# Vsense_Thermistor.net
KiCad netlist of a schematic drawn in Altium Designer
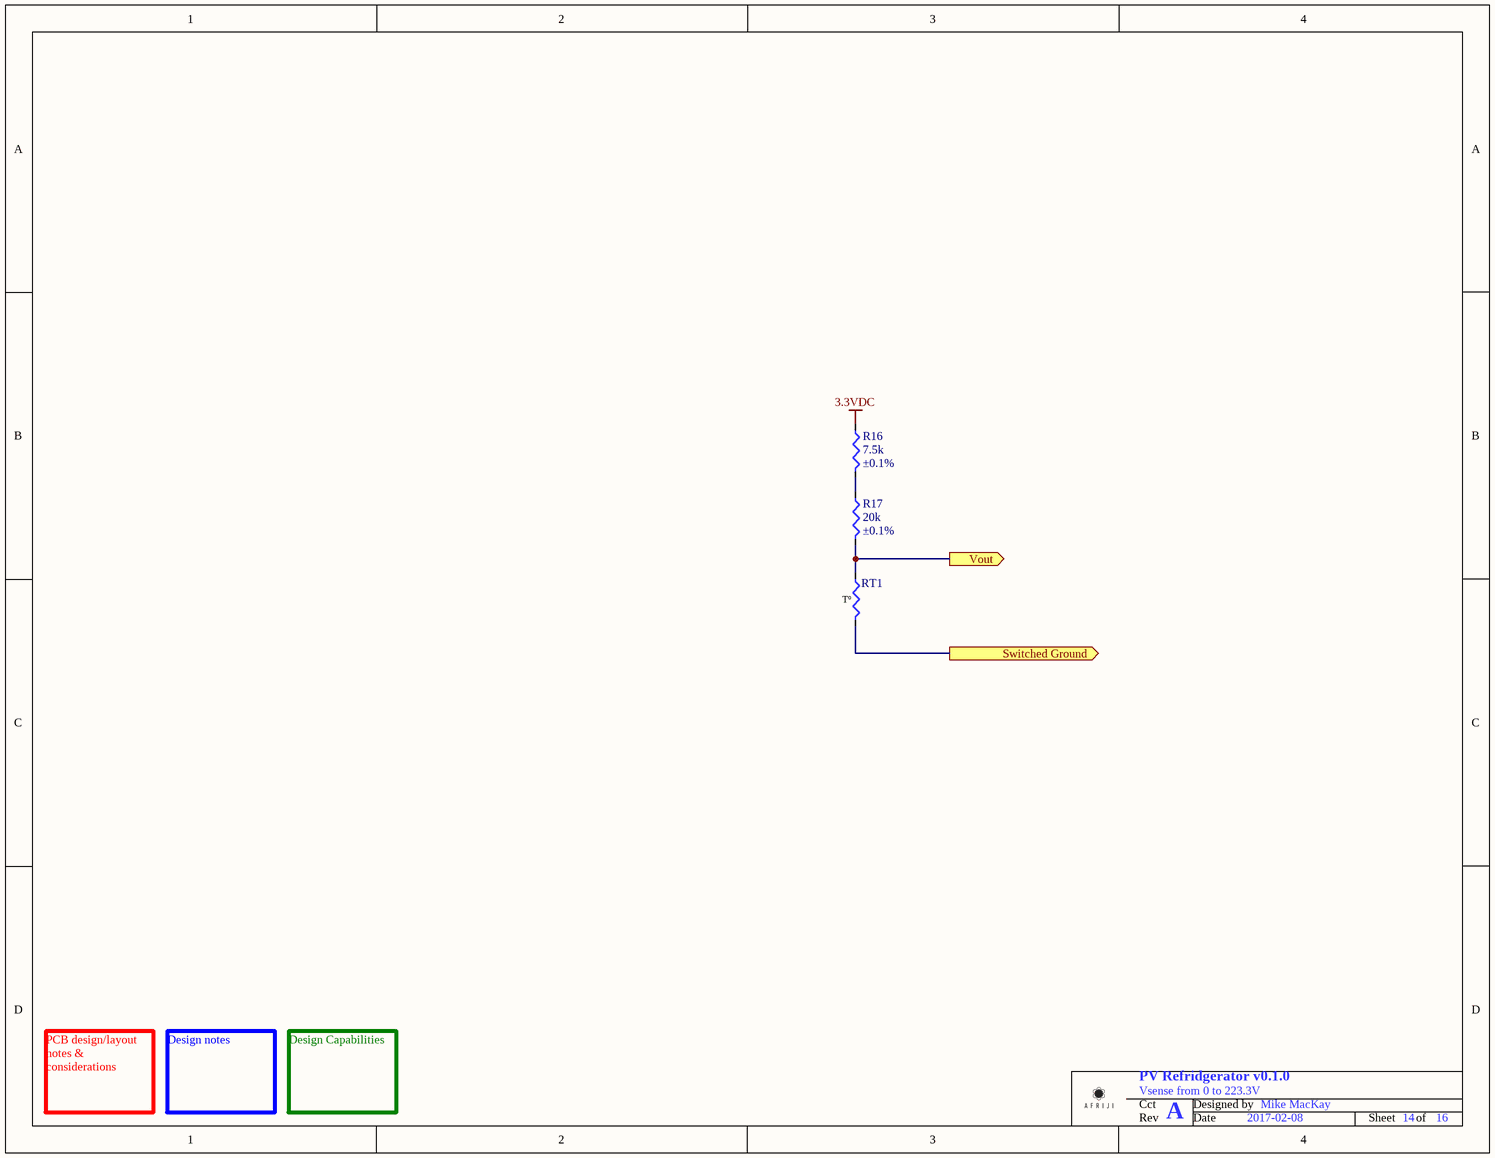
[diagram p0: Vsense Thermistor.SchDoc]

(export (version "E")
  (design (tool "Eeschema 10.0.6"))
  (components
    (comp (ref "R16")
      (value "Template - Resistor")
      (footprint "R0603")
      (description "Resistor")
      (fields
        (field (name "MANUFACTURER") "Yageo")
        (field (name "MANUFACTURER PART NUMBER") "RT0603BRD077K5L")
        (field (name "RESISTANCE (OHMS)") "7.5k")
        (field (name "TOLERANCE") "±0.1%")
      )
      (libsource (lib "Integrated Component Library") (part "Template - Resistor"))
    )
    (comp (ref "R17")
      (value "Template - Resistor")
      (footprint "R0603")
      (description "Resistor")
      (fields
        (field (name "MANUFACTURER") "Yageo")
        (field (name "MANUFACTURER PART NUMBER") "RT0603BRD0720KL")
        (field (name "RESISTANCE (OHMS)") "20k")
        (field (name "TOLERANCE") "±0.1%")
      )
      (libsource (lib "Integrated Component Library") (part "Template - Resistor"))
    )
    (comp (ref "RT1")
      (value "Tº")
      (footprint "Connector - MTA-100 2 Position Friction Lock")
      (description "Resistor")
      (fields
        (field (name "MANUFACTURER") "Murata Electronics North America")
        (field (name "MANUFACTURER PART NUMBER") "NXFT15XH103FA2B025")
      )
      (libsource (lib "altium-import") (part "root_0_Thermistor 10k Type J_"))
    )
  )
  (nets
    (net (code "1") (name "/Switched Ground") (class "Default")
      (node (ref "RT1") (pin "1") (pinfunction "1_1") (pintype "passive"))
    )
    (net (code "2") (name "/Vout") (class "Default")
      (node (ref "R17") (pin "1") (pinfunction "1_1") (pintype "passive"))
      (node (ref "RT1") (pin "2") (pinfunction "2_2") (pintype "passive"))
    )
    (net (code "3") (name "3.3VDC") (class "Default")
      (node (ref "R16") (pin "2") (pinfunction "2_2") (pintype "passive"))
    )
    (net (code "4") (name "Net-(R16-Pad1)") (class "Default")
      (node (ref "R16") (pin "1") (pinfunction "1_1") (pintype "passive"))
      (node (ref "R17") (pin "2") (pinfunction "2_2") (pintype "passive"))
    )
  )
)
